# uv-dosimeter-featherwing-mk-2_2.net
KiCad netlist of a schematic drawn in EAGLE
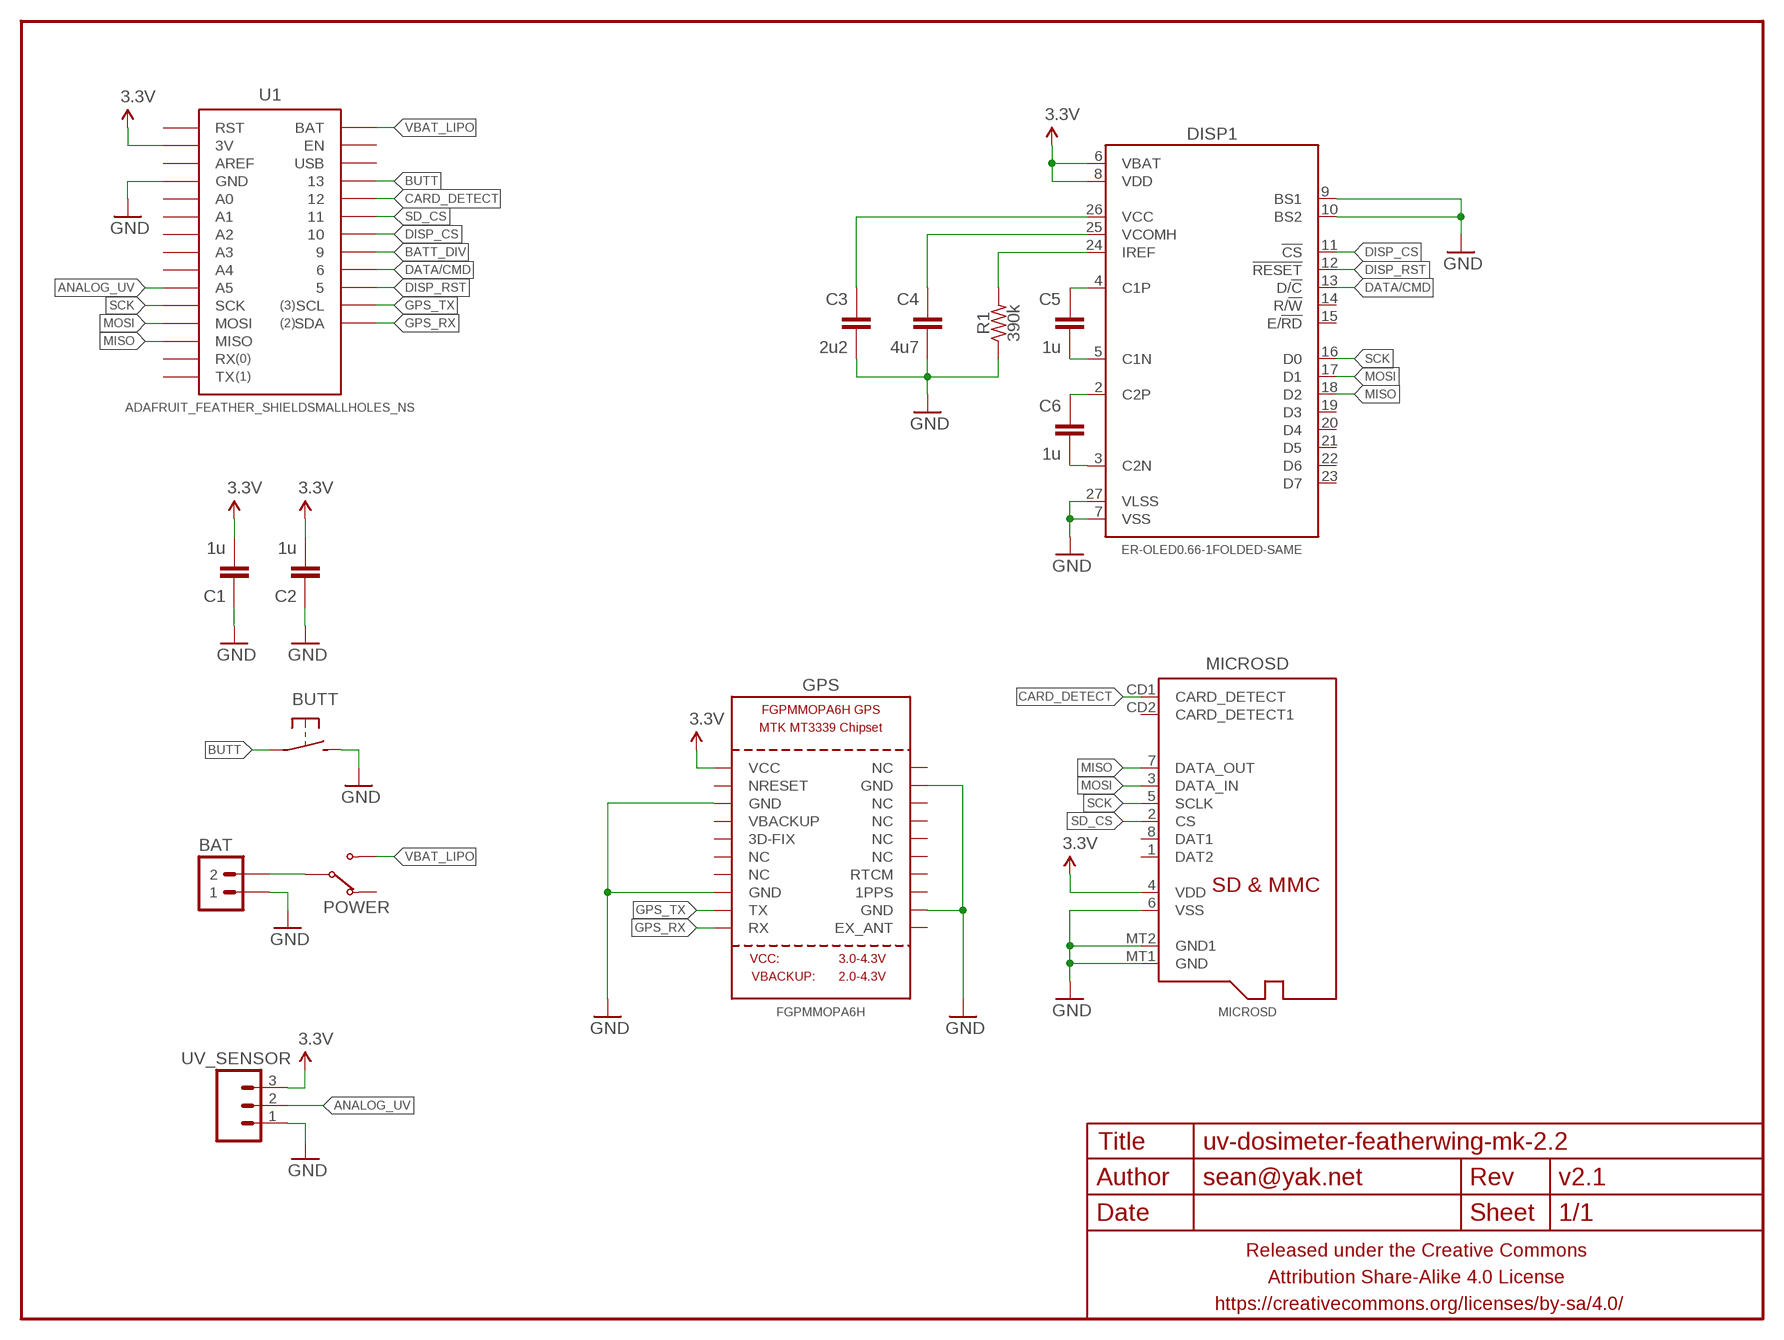
[diagram p0: schematic, sheet 1]

(export (version "E")
  (design (tool "Eeschema 10.0.6"))
  (components
    (comp (ref "BAT")
      (value "M02JST-2MM-SMT")
      (footprint "eagle-import:JST-2-SMD")
      (libsource (lib "eagle-import") (part "M02JST-2MM-SMT"))
    )
    (comp (ref "BUTT")
      (value "SPST-NO-TACT3MM-PTH-SMALL-PADS")
      (footprint "eagle-import:DTS-3-SMALL-PADS")
      (libsource (lib "eagle-import") (part "SPST-NO-TACT3MM-PTH-SMALL-PADS"))
    )
    (comp (ref "C1")
      (value "1u")
      (footprint "eagle-import:C0603")
      (libsource (lib "eagle-import") (part "CAPACITOR-CERAMICC0603"))
    )
    (comp (ref "C2")
      (value "1u")
      (footprint "eagle-import:C0603")
      (libsource (lib "eagle-import") (part "CAPACITOR-CERAMICC0603"))
    )
    (comp (ref "C3")
      (value "2u2")
      (footprint "eagle-import:C0603")
      (libsource (lib "eagle-import") (part "CAPACITOR-CERAMICC0603"))
    )
    (comp (ref "C4")
      (value "4u7")
      (footprint "eagle-import:C0603")
      (libsource (lib "eagle-import") (part "CAPACITOR-CERAMICC0603"))
    )
    (comp (ref "C5")
      (value "1u")
      (footprint "eagle-import:C0603")
      (libsource (lib "eagle-import") (part "CAPACITOR-CERAMICC0603"))
    )
    (comp (ref "C6")
      (value "1u")
      (footprint "eagle-import:C0603")
      (libsource (lib "eagle-import") (part "CAPACITOR-CERAMICC0603"))
    )
    (comp (ref "DISP1")
      (value "ER-OLED0.66-1FOLDED-SAME")
      (footprint "eagle-import:ER-OLED0.66-1-FOLDED-SAME")
      (libsource (lib "eagle-import") (part "ER-OLED0.66-1FOLDED-SAME"))
    )
    (comp (ref "FRAME1")
      (value "FRAME-LETTERNO_PACKAGE")
      (footprint "eagle-import:DUMMY")
      (fields (field (name "DESIGNER") "sean@yak.net") (field (name "VERSION") "v2.1"))
      (libsource (lib "eagle-import") (part "FRAME-LETTERNO_PACKAGE"))
    )
    (comp (ref "GPS")
      (value "FGPMMOPA6H")
      (footprint "eagle-import:FGPMMOPA6H")
      (libsource (lib "eagle-import") (part "GPS_FGPMMOPA6H"))
    )
    (comp (ref "MICROSD")
      (value "MICROSD")
      (footprint "eagle-import:MICROSD")
      (libsource (lib "eagle-import") (part "MICROSD"))
    )
    (comp (ref "POWER")
      (value "SWITCH-SPDTPTH-VERT-2.54MM")
      (footprint "eagle-import:SWITCH-SPDT")
      (libsource (lib "eagle-import") (part "SWITCH-SPDTPTH-VERT-2.54MM"))
    )
    (comp (ref "R1")
      (value "390k")
      (footprint "eagle-import:R0603")
      (libsource (lib "eagle-import") (part "RESISTORR0603"))
    )
    (comp (ref "U1")
      (value "ADAFRUIT_FEATHER_SHIELDSMALLHOLES_NS")
      (footprint "eagle-import:ADAFRUIT_FEATHER_SMALLHOLES_NS")
      (libsource (lib "eagle-import") (part "ADAFRUIT_FEATHER_SHIELDSMALLHOLES_NS"))
    )
    (comp (ref "UV_SENSOR")
      (value "M03PTH-CENTERED")
      (footprint "eagle-import:1X03-CENTERED")
      (libsource (lib "eagle-import") (part "M03PTH-CENTERED"))
    )
  )
  (nets
    (net (code "1") (name "3.3V") (class "Default")
      (node (ref "C1") (pin "2") (pinfunction "2_2") (pintype "passive"))
      (node (ref "C2") (pin "2") (pinfunction "2_2") (pintype "passive"))
      (node (ref "DISP1") (pin "6") (pinfunction "VBAT_6") (pintype "bidirectional"))
      (node (ref "DISP1") (pin "8") (pinfunction "VDD_8") (pintype "bidirectional"))
      (node (ref "GPS") (pin "P$1") (pinfunction "VCC_P$1") (pintype "bidirectional"))
      (node (ref "MICROSD") (pin "4") (pinfunction "VDD_4") (pintype "power_in"))
      (node (ref "U1") (pin "3V") (pinfunction "3V_3V") (pintype "bidirectional"))
      (node (ref "UV_SENSOR") (pin "3") (pinfunction "3_3") (pintype "passive"))
    )
    (net (code "2") (name "ANALOG_UV") (class "Default")
      (node (ref "U1") (pin "A5") (pinfunction "A5_A5") (pintype "bidirectional"))
      (node (ref "UV_SENSOR") (pin "2") (pinfunction "2_2") (pintype "passive"))
    )
    (net (code "3") (name "BATT_DIV") (class "Default")
      (node (ref "U1") (pin "9") (pinfunction "9_9") (pintype "bidirectional"))
    )
    (net (code "4") (name "BUTT") (class "Default")
      (node (ref "BUTT") (pin "1") (pinfunction "1_1") (pintype "passive"))
      (node (ref "U1") (pin "13") (pinfunction "13_13") (pintype "bidirectional"))
    )
    (net (code "5") (name "CARD_DETECT") (class "Default")
      (node (ref "MICROSD") (pin "CD1") (pinfunction "CARD_DETECT_CD1") (pintype "passive"))
      (node (ref "U1") (pin "12") (pinfunction "12_12") (pintype "bidirectional"))
    )
    (net (code "6") (name "DATA{slash}CMD") (class "Default")
      (node (ref "DISP1") (pin "13") (pinfunction "D/~{C}_13") (pintype "bidirectional"))
      (node (ref "U1") (pin "6") (pinfunction "6_6") (pintype "bidirectional"))
    )
    (net (code "7") (name "DISP_CS") (class "Default")
      (node (ref "DISP1") (pin "11") (pinfunction "~{CS}_11") (pintype "bidirectional"))
      (node (ref "U1") (pin "10") (pinfunction "10_10") (pintype "bidirectional"))
    )
    (net (code "8") (name "DISP_RST") (class "Default")
      (node (ref "DISP1") (pin "12") (pinfunction "~{RESET}_12") (pintype "bidirectional"))
      (node (ref "U1") (pin "5") (pinfunction "5_5") (pintype "bidirectional"))
    )
    (net (code "9") (name "GND") (class "Default")
      (node (ref "BAT") (pin "2") (pinfunction "1_2") (pintype "passive"))
      (node (ref "BUTT") (pin "2") (pinfunction "2_2") (pintype "passive"))
      (node (ref "C1") (pin "1") (pinfunction "1_1") (pintype "passive"))
      (node (ref "C2") (pin "1") (pinfunction "1_1") (pintype "passive"))
      (node (ref "C3") (pin "2") (pinfunction "2_2") (pintype "passive"))
      (node (ref "C4") (pin "2") (pinfunction "2_2") (pintype "passive"))
      (node (ref "DISP1") (pin "10") (pinfunction "BS2_10") (pintype "bidirectional"))
      (node (ref "DISP1") (pin "27") (pinfunction "VLSS_27") (pintype "bidirectional"))
      (node (ref "DISP1") (pin "7") (pinfunction "VSS_7") (pintype "bidirectional"))
      (node (ref "DISP1") (pin "9") (pinfunction "BS1_9") (pintype "bidirectional"))
      (node (ref "GPS") (pin "P$12") (pinfunction "GND_P$12") (pintype "bidirectional"))
      (node (ref "GPS") (pin "P$19") (pinfunction "GND_P$19") (pintype "bidirectional"))
      (node (ref "GPS") (pin "P$3") (pinfunction "GND_P$3") (pintype "bidirectional"))
      (node (ref "GPS") (pin "P$8") (pinfunction "GND_P$8") (pintype "bidirectional"))
      (node (ref "MICROSD") (pin "6") (pinfunction "VSS_6") (pintype "power_in"))
      (node (ref "MICROSD") (pin "MT1") (pinfunction "GND_MT1") (pintype "power_in"))
      (node (ref "MICROSD") (pin "MT2") (pinfunction "GND1_MT2") (pintype "power_in"))
      (node (ref "R1") (pin "1") (pinfunction "1_1") (pintype "passive"))
      (node (ref "U1") (pin "GND@0") (pinfunction "GND_GND@0") (pintype "bidirectional"))
      (node (ref "U1") (pin "GND@1") (pinfunction "GND_GND@1") (pintype "bidirectional"))
      (node (ref "UV_SENSOR") (pin "1") (pinfunction "1_1") (pintype "passive"))
    )
    (net (code "10") (name "GPS_RX") (class "Default")
      (node (ref "GPS") (pin "P$10") (pinfunction "RX_P$10") (pintype "bidirectional"))
      (node (ref "U1") (pin "SDA") (pinfunction "SDA_SDA") (pintype "bidirectional"))
    )
    (net (code "11") (name "GPS_TX") (class "Default")
      (node (ref "GPS") (pin "P$9") (pinfunction "TX_P$9") (pintype "bidirectional"))
      (node (ref "U1") (pin "SCL") (pinfunction "SCL_SCL") (pintype "bidirectional"))
    )
    (net (code "12") (name "MISO") (class "Default")
      (node (ref "DISP1") (pin "18") (pinfunction "D2_18") (pintype "bidirectional"))
      (node (ref "MICROSD") (pin "7") (pinfunction "DATA_OUT_7") (pintype "output"))
      (node (ref "U1") (pin "MISO") (pinfunction "MISO_MISO") (pintype "bidirectional"))
    )
    (net (code "13") (name "MOSI") (class "Default")
      (node (ref "DISP1") (pin "17") (pinfunction "D1_17") (pintype "bidirectional"))
      (node (ref "MICROSD") (pin "3") (pinfunction "DATA_IN_3") (pintype "input"))
      (node (ref "U1") (pin "MOSI") (pinfunction "MOSI_MOSI") (pintype "bidirectional"))
    )
    (net (code "14") (name "Net-(BAT-2)") (class "Default")
      (node (ref "BAT") (pin "1") (pinfunction "2_1") (pintype "passive"))
      (node (ref "POWER") (pin "2") (pinfunction "COM_2") (pintype "passive"))
    )
    (net (code "15") (name "Net-(DISP1-C1N)") (class "Default")
      (node (ref "C5") (pin "2") (pinfunction "2_2") (pintype "passive"))
      (node (ref "DISP1") (pin "5") (pinfunction "C1N_5") (pintype "bidirectional"))
    )
    (net (code "16") (name "Net-(DISP1-C1P)") (class "Default")
      (node (ref "C5") (pin "1") (pinfunction "1_1") (pintype "passive"))
      (node (ref "DISP1") (pin "4") (pinfunction "C1P_4") (pintype "bidirectional"))
    )
    (net (code "17") (name "Net-(DISP1-C2N)") (class "Default")
      (node (ref "C6") (pin "2") (pinfunction "2_2") (pintype "passive"))
      (node (ref "DISP1") (pin "3") (pinfunction "C2N_3") (pintype "bidirectional"))
    )
    (net (code "18") (name "Net-(DISP1-C2P)") (class "Default")
      (node (ref "C6") (pin "1") (pinfunction "1_1") (pintype "passive"))
      (node (ref "DISP1") (pin "2") (pinfunction "C2P_2") (pintype "bidirectional"))
    )
    (net (code "19") (name "Net-(DISP1-IREF)") (class "Default")
      (node (ref "DISP1") (pin "24") (pinfunction "IREF_24") (pintype "bidirectional"))
      (node (ref "R1") (pin "2") (pinfunction "2_2") (pintype "passive"))
    )
    (net (code "20") (name "Net-(DISP1-VCC)") (class "Default")
      (node (ref "C3") (pin "1") (pinfunction "1_1") (pintype "passive"))
      (node (ref "DISP1") (pin "26") (pinfunction "VCC_26") (pintype "bidirectional"))
    )
    (net (code "21") (name "Net-(DISP1-VCOMH)") (class "Default")
      (node (ref "C4") (pin "1") (pinfunction "1_1") (pintype "passive"))
      (node (ref "DISP1") (pin "25") (pinfunction "VCOMH_25") (pintype "bidirectional"))
    )
    (net (code "22") (name "SCK") (class "Default")
      (node (ref "DISP1") (pin "16") (pinfunction "D0_16") (pintype "bidirectional"))
      (node (ref "MICROSD") (pin "5") (pinfunction "SCLK_5") (pintype "input"))
      (node (ref "U1") (pin "SCK") (pinfunction "SCK_SCK") (pintype "bidirectional"))
    )
    (net (code "23") (name "SD_CS") (class "Default")
      (node (ref "MICROSD") (pin "2") (pinfunction "CS_2") (pintype "input"))
      (node (ref "U1") (pin "11") (pinfunction "11_11") (pintype "bidirectional"))
    )
    (net (code "24") (name "VBAT_LIPO") (class "Default")
      (node (ref "POWER") (pin "3") (pinfunction "NO_3") (pintype "passive"))
      (node (ref "U1") (pin "BAT") (pinfunction "BAT_BAT") (pintype "bidirectional"))
    )
    (net (code "25") (name "unconnected-(DISP1-D3-Pad19)") (class "Default")
      (node (ref "DISP1") (pin "19") (pinfunction "D3_19") (pintype "bidirectional"))
    )
    (net (code "26") (name "unconnected-(DISP1-D4-Pad20)") (class "Default")
      (node (ref "DISP1") (pin "20") (pinfunction "D4_20") (pintype "bidirectional"))
    )
    (net (code "27") (name "unconnected-(DISP1-D5-Pad21)") (class "Default")
      (node (ref "DISP1") (pin "21") (pinfunction "D5_21") (pintype "bidirectional"))
    )
    (net (code "28") (name "unconnected-(DISP1-D6-Pad22)") (class "Default")
      (node (ref "DISP1") (pin "22") (pinfunction "D6_22") (pintype "bidirectional"))
    )
    (net (code "29") (name "unconnected-(DISP1-D7-Pad23)") (class "Default")
      (node (ref "DISP1") (pin "23") (pinfunction "D7_23") (pintype "bidirectional"))
    )
    (net (code "30") (name "unconnected-(DISP1-E{slash}~{RD}-Pad15)") (class "Default")
      (node (ref "DISP1") (pin "15") (pinfunction "E/~{RD}_15") (pintype "bidirectional"))
    )
    (net (code "31") (name "unconnected-(DISP1-R{slash}~{W}-Pad14)") (class "Default")
      (node (ref "DISP1") (pin "14") (pinfunction "R/~{W}_14") (pintype "bidirectional"))
    )
    (net (code "32") (name "unconnected-(GPS-1PPS-PadP$13)") (class "Default")
      (node (ref "GPS") (pin "P$13") (pinfunction "1PPS_P$13") (pintype "bidirectional"))
    )
    (net (code "33") (name "unconnected-(GPS-3D-FIX-PadP$5)") (class "Default")
      (node (ref "GPS") (pin "P$5") (pinfunction "3D-FIX_P$5") (pintype "bidirectional"))
    )
    (net (code "34") (name "unconnected-(GPS-EX_ANT-PadP$11)") (class "Default")
      (node (ref "GPS") (pin "P$11") (pinfunction "EX_ANT_P$11") (pintype "bidirectional"))
    )
    (net (code "35") (name "unconnected-(GPS-NC-PadP$6)") (class "Default")
      (node (ref "GPS") (pin "P$6") (pinfunction "NC_P$6") (pintype "bidirectional"))
    )
    (net (code "36") (name "unconnected-(GPS-NC-PadP$7)") (class "Default")
      (node (ref "GPS") (pin "P$7") (pinfunction "NC_P$7") (pintype "bidirectional"))
    )
    (net (code "37") (name "unconnected-(GPS-NC-PadP$15)") (class "Default")
      (node (ref "GPS") (pin "P$15") (pinfunction "NC_P$15") (pintype "bidirectional"))
    )
    (net (code "38") (name "unconnected-(GPS-NC-PadP$16)") (class "Default")
      (node (ref "GPS") (pin "P$16") (pinfunction "NC_P$16") (pintype "bidirectional"))
    )
    (net (code "39") (name "unconnected-(GPS-NC-PadP$17)") (class "Default")
      (node (ref "GPS") (pin "P$17") (pinfunction "NC_P$17") (pintype "bidirectional"))
    )
    (net (code "40") (name "unconnected-(GPS-NC-PadP$18)") (class "Default")
      (node (ref "GPS") (pin "P$18") (pinfunction "NC_P$18") (pintype "bidirectional"))
    )
    (net (code "41") (name "unconnected-(GPS-NC-PadP$20)") (class "Default")
      (node (ref "GPS") (pin "P$20") (pinfunction "NC_P$20") (pintype "bidirectional"))
    )
    (net (code "42") (name "unconnected-(GPS-NRESET-PadP$2)") (class "Default")
      (node (ref "GPS") (pin "P$2") (pinfunction "NRESET_P$2") (pintype "bidirectional"))
    )
    (net (code "43") (name "unconnected-(GPS-RTCM-PadP$14)") (class "Default")
      (node (ref "GPS") (pin "P$14") (pinfunction "RTCM_P$14") (pintype "bidirectional"))
    )
    (net (code "44") (name "unconnected-(GPS-VBACKUP-PadP$4)") (class "Default")
      (node (ref "GPS") (pin "P$4") (pinfunction "VBACKUP_P$4") (pintype "bidirectional"))
    )
    (net (code "45") (name "unconnected-(MICROSD-CARD_DETECT1-PadCD2)") (class "Default")
      (node (ref "MICROSD") (pin "CD2") (pinfunction "CARD_DETECT1_CD2") (pintype "passive"))
    )
    (net (code "46") (name "unconnected-(MICROSD-DAT1-Pad8)") (class "Default")
      (node (ref "MICROSD") (pin "8") (pinfunction "DAT1_8") (pintype "bidirectional"))
    )
    (net (code "47") (name "unconnected-(MICROSD-DAT2-Pad1)") (class "Default")
      (node (ref "MICROSD") (pin "1") (pinfunction "DAT2_1") (pintype "bidirectional"))
    )
    (net (code "48") (name "unconnected-(POWER-NC-Pad1)") (class "Default")
      (node (ref "POWER") (pin "1") (pinfunction "NC_1") (pintype "passive"))
    )
    (net (code "49") (name "unconnected-(U1-PadA0)") (class "Default")
      (node (ref "U1") (pin "A0") (pinfunction "A0_A0") (pintype "bidirectional"))
    )
    (net (code "50") (name "unconnected-(U1-PadA1)") (class "Default")
      (node (ref "U1") (pin "A1") (pinfunction "A1_A1") (pintype "bidirectional"))
    )
    (net (code "51") (name "unconnected-(U1-PadA2)") (class "Default")
      (node (ref "U1") (pin "A2") (pinfunction "A2_A2") (pintype "bidirectional"))
    )
    (net (code "52") (name "unconnected-(U1-PadA3)") (class "Default")
      (node (ref "U1") (pin "A3") (pinfunction "A3_A3") (pintype "bidirectional"))
    )
    (net (code "53") (name "unconnected-(U1-PadA4)") (class "Default")
      (node (ref "U1") (pin "A4") (pinfunction "A4_A4") (pintype "bidirectional"))
    )
    (net (code "54") (name "unconnected-(U1-PadAREF)") (class "Default")
      (node (ref "U1") (pin "AREF") (pinfunction "AREF_AREF") (pintype "bidirectional"))
    )
    (net (code "55") (name "unconnected-(U1-PadEN)") (class "Default")
      (node (ref "U1") (pin "EN") (pinfunction "EN_EN") (pintype "bidirectional"))
    )
    (net (code "56") (name "unconnected-(U1-PadRST)") (class "Default")
      (node (ref "U1") (pin "RST") (pinfunction "RST_RST") (pintype "bidirectional"))
    )
    (net (code "57") (name "unconnected-(U1-PadRX)") (class "Default")
      (node (ref "U1") (pin "RX") (pinfunction "RX_RX") (pintype "bidirectional"))
    )
    (net (code "58") (name "unconnected-(U1-PadTX)") (class "Default")
      (node (ref "U1") (pin "TX") (pinfunction "TX_TX") (pintype "bidirectional"))
    )
    (net (code "59") (name "unconnected-(U1-PadUSB)") (class "Default")
      (node (ref "U1") (pin "USB") (pinfunction "USB_USB") (pintype "bidirectional"))
    )
  )
)
